# TFT_2_2-inch_ILI9341_Sch.net
KiCad netlist of a schematic drawn in Altium Designer
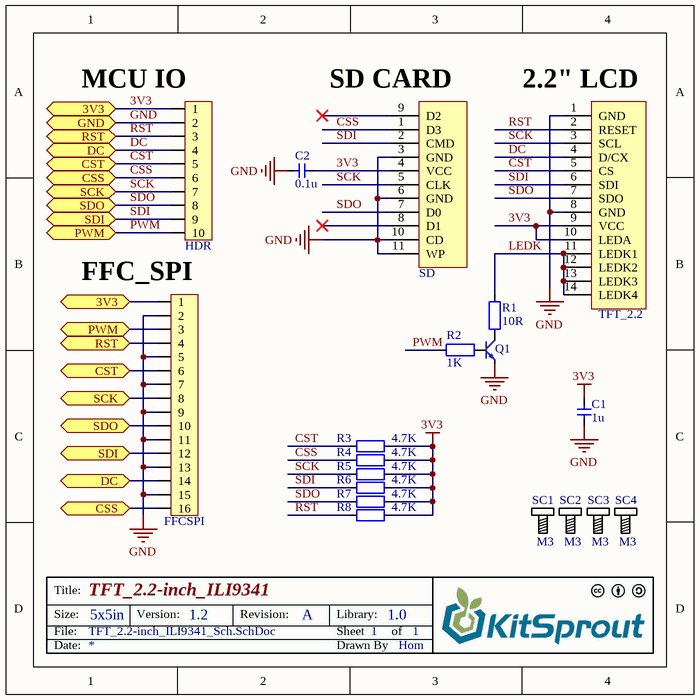
[diagram p0: TFT_2.2-inch_ILI9341_Sch.SchDoc]

(export (version "E")
  (design (tool "Eeschema 10.0.6"))
  (components
    (comp (ref "C1")
      (value "1u")
      (footprint "PCB_PassiveCap:CAP_0603")
      (description "Capacitor")
      (fields (field (name "Comment") "Cap_0603"))
      (libsource (lib "SCH_Passive") (part "Cap_0603"))
    )
    (comp (ref "C2")
      (value "0.1u")
      (footprint "PCB_PassiveCap:CAP_0603")
      (description "Capacitor")
      (fields (field (name "Comment") "Cap_0603"))
      (libsource (lib "SCH_Passive") (part "Cap_0603"))
    )
    (comp (ref "FFCSPI")
      (value "FFC_0.5_16")
      (footprint "PCB_ConnectorFFC:FFC_0.5_16")
      (description "FFC")
      (libsource (lib "SCH_Connector") (part "FFC_0.5_16"))
    )
    (comp (ref "HDR")
      (value "HDR1x10_2.54")
      (footprint "PCB_ConnectorHDR:HDR1X10_2.54_180")
      (description "Header")
      (libsource (lib "SCH_ConnectorHDR") (part "HDR1x10_2.54"))
    )
    (comp (ref "Q1")
      (value "BJT_NPN")
      (footprint "PCB_IntegratedCircuit:SOT23-3")
      (description "Transistor")
      (libsource (lib "SCH_Active") (part "BJT_NPN"))
    )
    (comp (ref "R1")
      (value "10R")
      (footprint "PCB_PassiveRes:RES_0603")
      (description "Resistor")
      (fields (field (name "Comment") "Res_0603"))
      (libsource (lib "") (part "Res_0603_1"))
    )
    (comp (ref "R2")
      (value "1K")
      (footprint "PCB_PassiveRes:RES_0603")
      (description "Resistor")
      (fields (field (name "Comment") "Res_0603"))
      (libsource (lib "SCH_Passive") (part "Res_0603"))
    )
    (comp (ref "R3")
      (value "4.7K")
      (footprint "PCB_PassiveRes:RES_0603")
      (description "Resistor")
      (fields (field (name "Comment") "Res_0603"))
      (libsource (lib "SCH_Passive") (part "Res_0603"))
    )
    (comp (ref "R4")
      (value "4.7K")
      (footprint "PCB_PassiveRes:RES_0603")
      (description "Resistor")
      (fields (field (name "Comment") "Res_0603"))
      (libsource (lib "SCH_Passive") (part "Res_0603"))
    )
    (comp (ref "R5")
      (value "4.7K")
      (footprint "PCB_PassiveRes:RES_0603")
      (description "Resistor")
      (fields (field (name "Comment") "Res_0603"))
      (libsource (lib "SCH_Passive") (part "Res_0603"))
    )
    (comp (ref "R6")
      (value "4.7K")
      (footprint "PCB_PassiveRes:RES_0603")
      (description "Resistor")
      (fields (field (name "Comment") "Res_0603"))
      (libsource (lib "SCH_Passive") (part "Res_0603"))
    )
    (comp (ref "R7")
      (value "4.7K")
      (footprint "PCB_PassiveRes:RES_0603")
      (description "Resistor")
      (fields (field (name "Comment") "Res_0603"))
      (libsource (lib "SCH_Passive") (part "Res_0603"))
    )
    (comp (ref "R8")
      (value "4.7K")
      (footprint "PCB_PassiveRes:RES_0603")
      (description "Resistor")
      (fields (field (name "Comment") "Res_0603"))
      (libsource (lib "SCH_Passive") (part "Res_0603"))
    )
    (comp (ref "SC1")
      (value "M3")
      (footprint "PCB_Mechanical:SCRREW_M3")
      (description "Screw")
      (libsource (lib "SCH_Mechanical") (part "Screw_M3"))
    )
    (comp (ref "SC2")
      (value "M3")
      (footprint "PCB_Mechanical:SCRREW_M3")
      (description "Screw")
      (libsource (lib "SCH_Mechanical") (part "Screw_M3"))
    )
    (comp (ref "SC3")
      (value "M3")
      (footprint "PCB_Mechanical:SCRREW_M3")
      (description "Screw")
      (libsource (lib "SCH_Mechanical") (part "Screw_M3"))
    )
    (comp (ref "SC4")
      (value "M3")
      (footprint "PCB_Mechanical:SCRREW_M3")
      (description "Screw")
      (libsource (lib "SCH_Mechanical") (part "Screw_M3"))
    )
    (comp (ref "SD")
      (value "SD_Card")
      (footprint "PCB_SDCard:SD_Card_1")
      (description "SD")
      (libsource (lib "SCH_SDCard") (part "SD_Card"))
    )
    (comp (ref "TFT_2.2")
      (value "TFT_2.2_ILI9341")
      (footprint "PCB_Module:TFT_2.2_320x240_ILI9341")
      (description "TFT")
      (libsource (lib "SCH_Module") (part "TFT_2.2_ILI9341"))
    )
  )
  (nets
    (net (code "1") (name "/CSS") (class "Default")
      (node (ref "FFCSPI") (pin "16") (pinfunction "16_16") (pintype "passive"))
      (node (ref "HDR") (pin "6") (pinfunction "6_6") (pintype "passive"))
      (node (ref "R4") (pin "2") (pinfunction "2_2") (pintype "passive"))
      (node (ref "SD") (pin "1") (pinfunction "D3_1") (pintype "passive"))
    )
    (net (code "2") (name "/CST") (class "Default")
      (node (ref "FFCSPI") (pin "6") (pinfunction "6_6") (pintype "passive"))
      (node (ref "HDR") (pin "5") (pinfunction "5_5") (pintype "passive"))
      (node (ref "R3") (pin "2") (pinfunction "2_2") (pintype "passive"))
      (node (ref "TFT_2.2") (pin "5") (pinfunction "CS_5") (pintype "passive"))
    )
    (net (code "3") (name "/DC") (class "Default")
      (node (ref "FFCSPI") (pin "14") (pinfunction "14_14") (pintype "passive"))
      (node (ref "HDR") (pin "4") (pinfunction "4_4") (pintype "passive"))
      (node (ref "TFT_2.2") (pin "4") (pinfunction "D/CX_4") (pintype "passive"))
    )
    (net (code "4") (name "/LEDK") (class "Default")
      (node (ref "R1") (pin "2") (pinfunction "2_2") (pintype "passive"))
      (node (ref "TFT_2.2") (pin "11") (pinfunction "LEDK1_11") (pintype "passive"))
      (node (ref "TFT_2.2") (pin "12") (pinfunction "LEDK2_12") (pintype "passive"))
      (node (ref "TFT_2.2") (pin "13") (pinfunction "LEDK3_13") (pintype "passive"))
      (node (ref "TFT_2.2") (pin "14") (pinfunction "LEDK4_14") (pintype "passive"))
    )
    (net (code "5") (name "/PWM") (class "Default")
      (node (ref "FFCSPI") (pin "3") (pinfunction "3_3") (pintype "passive"))
      (node (ref "HDR") (pin "10") (pinfunction "10_10") (pintype "passive"))
      (node (ref "R2") (pin "2") (pinfunction "2_2") (pintype "passive"))
    )
    (net (code "6") (name "/RST") (class "Default")
      (node (ref "FFCSPI") (pin "4") (pinfunction "4_4") (pintype "passive"))
      (node (ref "HDR") (pin "3") (pinfunction "3_3") (pintype "passive"))
      (node (ref "R8") (pin "2") (pinfunction "2_2") (pintype "passive"))
      (node (ref "TFT_2.2") (pin "2") (pinfunction "RESET_2") (pintype "passive"))
    )
    (net (code "7") (name "/SCK") (class "Default")
      (node (ref "FFCSPI") (pin "8") (pinfunction "8_8") (pintype "passive"))
      (node (ref "HDR") (pin "7") (pinfunction "7_7") (pintype "passive"))
      (node (ref "R5") (pin "2") (pinfunction "2_2") (pintype "passive"))
      (node (ref "SD") (pin "5") (pinfunction "CLK_5") (pintype "passive"))
      (node (ref "TFT_2.2") (pin "3") (pinfunction "SCL_3") (pintype "passive"))
    )
    (net (code "8") (name "/SDI") (class "Default")
      (node (ref "FFCSPI") (pin "12") (pinfunction "12_12") (pintype "passive"))
      (node (ref "HDR") (pin "9") (pinfunction "9_9") (pintype "passive"))
      (node (ref "R6") (pin "2") (pinfunction "2_2") (pintype "passive"))
      (node (ref "SD") (pin "2") (pinfunction "CMD_2") (pintype "passive"))
      (node (ref "TFT_2.2") (pin "6") (pinfunction "SDI_6") (pintype "passive"))
    )
    (net (code "9") (name "/SDO") (class "Default")
      (node (ref "FFCSPI") (pin "10") (pinfunction "10_10") (pintype "passive"))
      (node (ref "HDR") (pin "8") (pinfunction "8_8") (pintype "passive"))
      (node (ref "R7") (pin "2") (pinfunction "2_2") (pintype "passive"))
      (node (ref "SD") (pin "7") (pinfunction "D0_7") (pintype "passive"))
      (node (ref "TFT_2.2") (pin "7") (pinfunction "SDO_7") (pintype "passive"))
    )
    (net (code "10") (name "3V3") (class "Default")
      (node (ref "C1") (pin "2") (pinfunction "2_2") (pintype "passive"))
      (node (ref "C2") (pin "2") (pinfunction "2_2") (pintype "passive"))
      (node (ref "FFCSPI") (pin "1") (pinfunction "1_1") (pintype "passive"))
      (node (ref "HDR") (pin "1") (pinfunction "1_1") (pintype "passive"))
      (node (ref "R3") (pin "1") (pinfunction "1_1") (pintype "passive"))
      (node (ref "R4") (pin "1") (pinfunction "1_1") (pintype "passive"))
      (node (ref "R5") (pin "1") (pinfunction "1_1") (pintype "passive"))
      (node (ref "R6") (pin "1") (pinfunction "1_1") (pintype "passive"))
      (node (ref "R7") (pin "1") (pinfunction "1_1") (pintype "passive"))
      (node (ref "R8") (pin "1") (pinfunction "1_1") (pintype "passive"))
      (node (ref "SD") (pin "4") (pinfunction "VCC_4") (pintype "passive"))
      (node (ref "TFT_2.2") (pin "10") (pinfunction "LEDA_10") (pintype "passive"))
      (node (ref "TFT_2.2") (pin "9") (pinfunction "VCC_9") (pintype "passive"))
    )
    (net (code "11") (name "GND") (class "Default")
      (node (ref "C1") (pin "1") (pinfunction "1_1") (pintype "passive"))
      (node (ref "C2") (pin "1") (pinfunction "1_1") (pintype "passive"))
      (node (ref "FFCSPI") (pin "11") (pinfunction "11_11") (pintype "passive"))
      (node (ref "FFCSPI") (pin "13") (pinfunction "13_13") (pintype "passive"))
      (node (ref "FFCSPI") (pin "15") (pinfunction "15_15") (pintype "passive"))
      (node (ref "FFCSPI") (pin "2") (pinfunction "2_2") (pintype "passive"))
      (node (ref "FFCSPI") (pin "5") (pinfunction "5_5") (pintype "passive"))
      (node (ref "FFCSPI") (pin "7") (pinfunction "7_7") (pintype "passive"))
      (node (ref "FFCSPI") (pin "9") (pinfunction "9_9") (pintype "passive"))
      (node (ref "HDR") (pin "2") (pinfunction "2_2") (pintype "passive"))
      (node (ref "Q1") (pin "2") (pinfunction "E_2") (pintype "passive"))
      (node (ref "SD") (pin "10") (pinfunction "CD_10") (pintype "passive"))
      (node (ref "SD") (pin "11") (pinfunction "WP_11") (pintype "passive"))
      (node (ref "SD") (pin "3") (pinfunction "GND_3") (pintype "passive"))
      (node (ref "SD") (pin "6") (pinfunction "GND_6") (pintype "passive"))
      (node (ref "TFT_2.2") (pin "1") (pinfunction "GND_1") (pintype "passive"))
      (node (ref "TFT_2.2") (pin "8") (pinfunction "GND_8") (pintype "passive"))
    )
    (net (code "12") (name "Net-(Q1-B)") (class "Default")
      (node (ref "Q1") (pin "1") (pinfunction "B_1") (pintype "passive"))
      (node (ref "R2") (pin "1") (pinfunction "1_1") (pintype "passive"))
    )
    (net (code "13") (name "Net-(Q1-C)") (class "Default")
      (node (ref "Q1") (pin "3") (pinfunction "C_3") (pintype "passive"))
      (node (ref "R1") (pin "1") (pinfunction "1_1") (pintype "passive"))
    )
    (net (code "14") (name "unconnected-(SD-D1-Pad8)") (class "Default")
      (node (ref "SD") (pin "8") (pinfunction "D1_8") (pintype "passive+no_connect"))
    )
    (net (code "15") (name "unconnected-(SD-D2-Pad9)") (class "Default")
      (node (ref "SD") (pin "9") (pinfunction "D2_9") (pintype "passive+no_connect"))
    )
  )
)
